# 3V3StepDown.net
KiCad netlist of a schematic drawn in Altium Designer
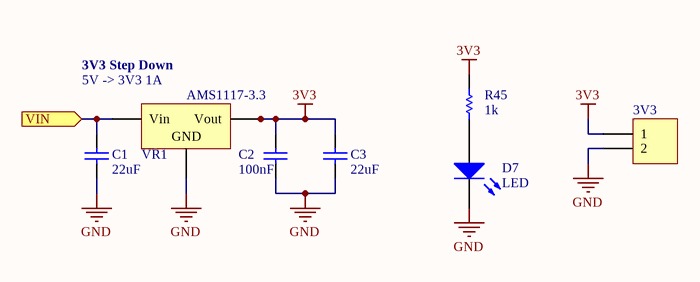
[diagram p0: 3V3StepDown.SchDoc]

(export (version "E")
  (design (tool "Eeschema 10.0.6"))
  (components
    (comp (ref "3V3")
      (value "Header 2")
      (footprint "HDR1X2")
      (description "Header, 2-Pin")
      (fields (field (name "PUBLISHER") "Altium Limited"))
      (libsource (lib "Miscellaneous Connectors") (part "Header 2"))
    )
    (comp (ref "C1")
      (value "22uF")
      (footprint "J1-0603")
      (description "Capacitor")
      (fields (field (name "Comment") "Cap") (field (name "PUBLISHER") "Altium Limited"))
      (libsource (lib "Miscellaneous Devices") (part "Cap"))
    )
    (comp (ref "C2")
      (value "100nF")
      (footprint "J1-0603")
      (description "Capacitor")
      (fields (field (name "Comment") "Cap") (field (name "PUBLISHER") "Altium Limited"))
      (libsource (lib "Miscellaneous Devices") (part "Cap"))
    )
    (comp (ref "C3")
      (value "22uF")
      (footprint "J1-0603")
      (description "Capacitor")
      (fields (field (name "Comment") "Cap") (field (name "PUBLISHER") "Altium Limited"))
      (libsource (lib "Miscellaneous Devices") (part "Cap"))
    )
    (comp (ref "D7")
      (value "LED")
      (footprint "J1-0603 LED")
      (fields (field (name "PUBLISHER") "Altium Limited"))
      (libsource (lib "sumo") (part "LED"))
    )
    (comp (ref "R45")
      (value "1k")
      (footprint "J1-0603")
      (description "Resistor")
      (fields (field (name "Comment") "Res1") (field (name "PUBLISHER") "Altium Limited"))
      (libsource (lib "Miscellaneous Devices") (part "Res1"))
    )
    (comp (ref "VR1")
      (value "AMS1117-3.3")
      (footprint "SOT223-4M")
      (description "Voltage Regulator")
      (fields (field (name "PUBLISHER") "Altium Limited"))
      (libsource (lib "sumo") (part "Volt Reg"))
    )
  )
  (nets
    (net (code "1") (name "/VIN") (class "Default")
      (node (ref "C1") (pin "1") (pinfunction "1_1") (pintype "passive"))
      (node (ref "VR1") (pin "3") (pinfunction "Vin_3") (pintype "passive"))
    )
    (net (code "2") (name "3V3") (class "Default")
      (node (ref "3V3") (pin "1") (pinfunction "1_1") (pintype "passive"))
      (node (ref "C2") (pin "2") (pinfunction "2_2") (pintype "passive"))
      (node (ref "C3") (pin "1") (pinfunction "1_1") (pintype "passive"))
      (node (ref "R45") (pin "2") (pinfunction "2_2") (pintype "passive"))
      (node (ref "VR1") (pin "2") (pinfunction "Vout_2") (pintype "passive"))
      (node (ref "VR1") (pin "4") (pinfunction "Vout_4") (pintype "passive"))
    )
    (net (code "3") (name "GND") (class "Default")
      (node (ref "3V3") (pin "2") (pinfunction "2_2") (pintype "passive"))
      (node (ref "C1") (pin "2") (pinfunction "2_2") (pintype "passive"))
      (node (ref "C2") (pin "1") (pinfunction "1_1") (pintype "passive"))
      (node (ref "C3") (pin "2") (pinfunction "2_2") (pintype "passive"))
      (node (ref "D7") (pin "2") (pinfunction "K_2") (pintype "passive"))
      (node (ref "VR1") (pin "1") (pinfunction "GND_1") (pintype "passive"))
    )
    (net (code "4") (name "Net-(D7-A)") (class "Default")
      (node (ref "D7") (pin "1") (pinfunction "A_1") (pintype "passive"))
      (node (ref "R45") (pin "1") (pinfunction "1_1") (pintype "passive"))
    )
  )
)
